# board1_7.net
KiCad netlist of a schematic drawn in EAGLE
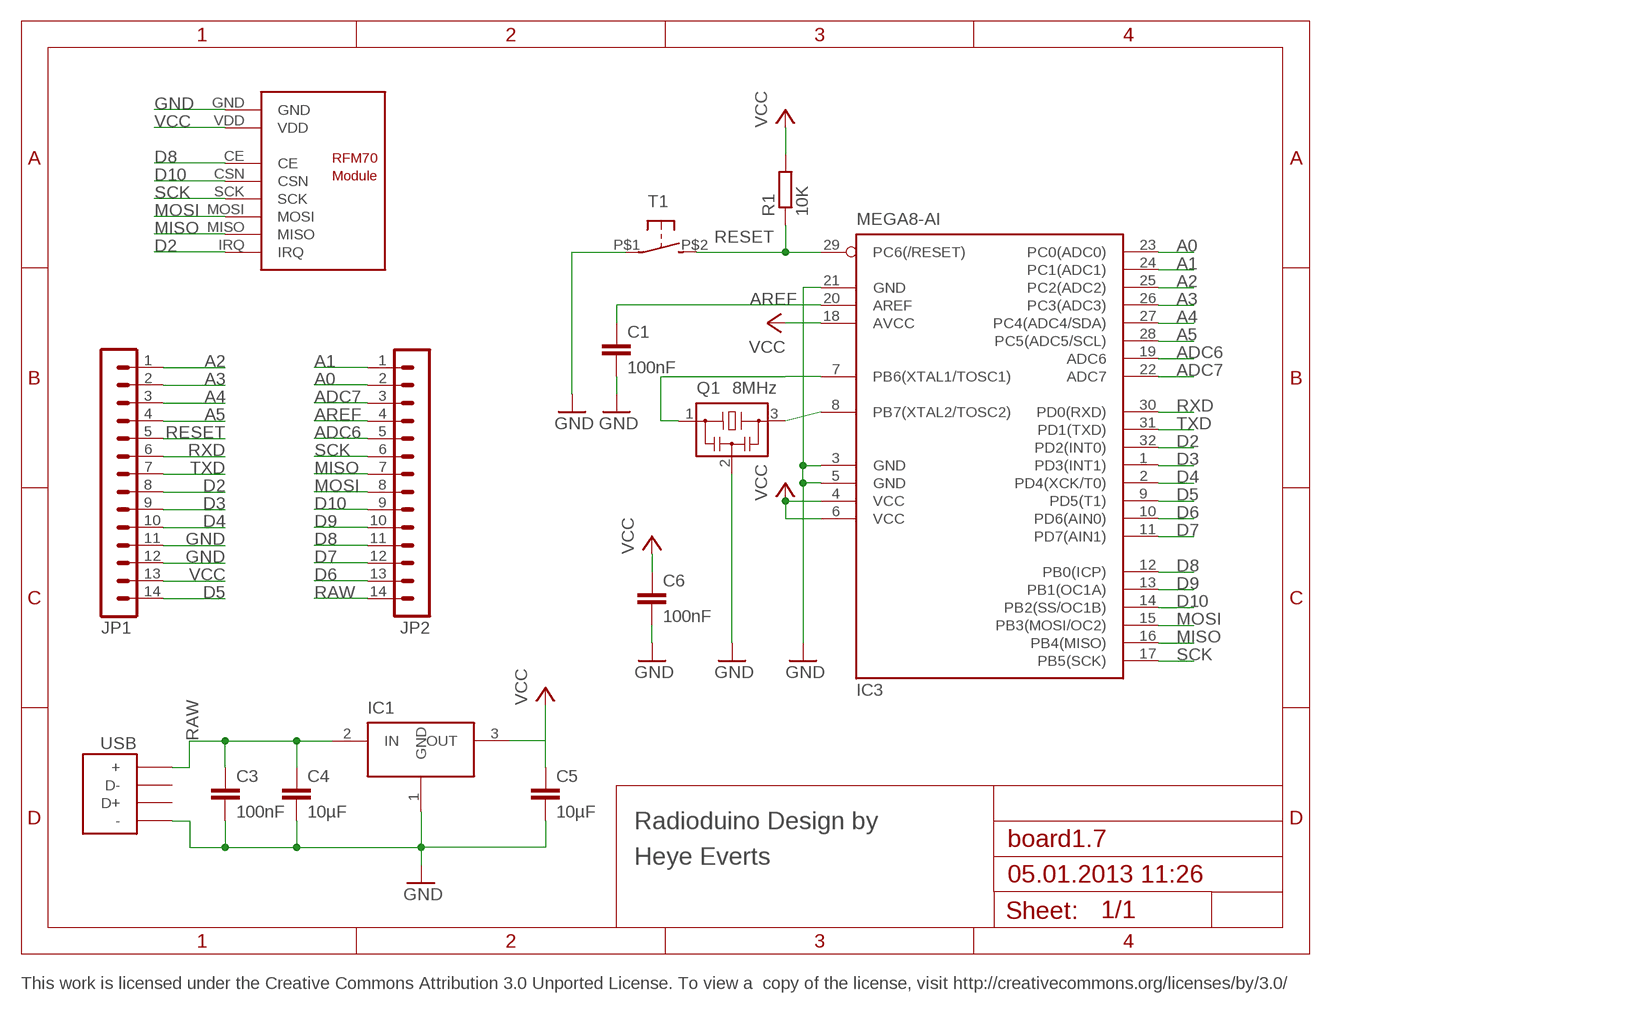
[diagram p0: schematic, sheet 1]

(export (version "E")
  (design (tool "Eeschema 10.0.6"))
  (components
    (comp (ref "C1")
      (value "100nF")
      (footprint "eagle-import:C0603K")
      (libsource (lib "eagle-import") (part "C-EUC0603K"))
    )
    (comp (ref "C3")
      (value "100nF")
      (footprint "eagle-import:C0603K")
      (libsource (lib "eagle-import") (part "C-EUC0603K"))
    )
    (comp (ref "C4")
      (value "10µF")
      (footprint "eagle-import:C0805K")
      (libsource (lib "eagle-import") (part "C-EUC0805K"))
    )
    (comp (ref "C5")
      (value "10µF")
      (footprint "eagle-import:C0805K")
      (libsource (lib "eagle-import") (part "C-EUC0805K"))
    )
    (comp (ref "C6")
      (value "100nF")
      (footprint "eagle-import:C0603K")
      (libsource (lib "eagle-import") (part "C-EUC0603K"))
    )
    (comp (ref "IC1")
      (value "TS1117CP33")
      (footprint "eagle-import:TO252")
      (libsource (lib "eagle-import") (part "TS1117CP33"))
    )
    (comp (ref "IC3")
      (value "MEGA8-AI")
      (footprint "eagle-import:TQFP32-08")
      (fields (field (name "MPN") "ATMEGA8-16AU"))
      (libsource (lib "eagle-import") (part "MEGA8-AI"))
    )
    (comp (ref "JP1")
      (value "MA14-1")
      (footprint "eagle-import:MA14-1")
      (fields (field (name "OC_FARNELL") "unknown") (field (name "OC_NEWARK") "unknown"))
      (libsource (lib "eagle-import") (part "MA14-1"))
    )
    (comp (ref "JP2")
      (value "MA14-1")
      (footprint "eagle-import:MA14-1")
      (libsource (lib "eagle-import") (part "MA14-1"))
    )
    (comp (ref "Q1")
      (value "8MHz")
      (footprint "eagle-import:CSTCE8M00G52")
      (libsource (lib "eagle-import") (part "CSTCE8M00G52"))
    )
    (comp (ref "R1")
      (value "10K")
      (footprint "eagle-import:R0603")
      (libsource (lib "eagle-import") (part "R-EU_R0603"))
    )
    (comp (ref "RFM70")
      (value "RFM70")
      (footprint "eagle-import:RFM70")
      (libsource (lib "eagle-import") (part "RFM70"))
    )
    (comp (ref "T1")
      (value "DTSM-3")
      (footprint "eagle-import:DTSM31N")
      (libsource (lib "eagle-import") (part "DTSM-3"))
    )
    (comp (ref "USB")
      (value "USB-MICRO-B-RS")
      (footprint "eagle-import:USB-MICRO-B-RS")
      (libsource (lib "eagle-import") (part "USB-MICRO-B-RS"))
    )
  )
  (nets
    (net (code "1") (name "/A0") (class "Default")
      (node (ref "IC3") (pin "23") (pinfunction "PC0(ADC0)_23") (pintype "bidirectional"))
      (node (ref "JP2") (pin "2") (pinfunction "2_2") (pintype "passive"))
    )
    (net (code "2") (name "/A1") (class "Default")
      (node (ref "IC3") (pin "24") (pinfunction "PC1(ADC1)_24") (pintype "bidirectional"))
      (node (ref "JP2") (pin "1") (pinfunction "1_1") (pintype "passive"))
    )
    (net (code "3") (name "/A2") (class "Default")
      (node (ref "IC3") (pin "25") (pinfunction "PC2(ADC2)_25") (pintype "bidirectional"))
      (node (ref "JP1") (pin "1") (pinfunction "1_1") (pintype "passive"))
    )
    (net (code "4") (name "/A3") (class "Default")
      (node (ref "IC3") (pin "26") (pinfunction "PC3(ADC3)_26") (pintype "bidirectional"))
      (node (ref "JP1") (pin "2") (pinfunction "2_2") (pintype "passive"))
    )
    (net (code "5") (name "/A4") (class "Default")
      (node (ref "IC3") (pin "27") (pinfunction "PC4(ADC4/SDA)_27") (pintype "bidirectional"))
      (node (ref "JP1") (pin "3") (pinfunction "3_3") (pintype "passive"))
    )
    (net (code "6") (name "/A5") (class "Default")
      (node (ref "IC3") (pin "28") (pinfunction "PC5(ADC5/SCL)_28") (pintype "bidirectional"))
      (node (ref "JP1") (pin "4") (pinfunction "4_4") (pintype "passive"))
    )
    (net (code "7") (name "/ADC6") (class "Default")
      (node (ref "IC3") (pin "19") (pinfunction "ADC6_19") (pintype "bidirectional"))
      (node (ref "JP2") (pin "5") (pinfunction "5_5") (pintype "passive"))
    )
    (net (code "8") (name "/ADC7") (class "Default")
      (node (ref "IC3") (pin "22") (pinfunction "ADC7_22") (pintype "bidirectional"))
      (node (ref "JP2") (pin "3") (pinfunction "3_3") (pintype "passive"))
    )
    (net (code "9") (name "/AREF") (class "Default")
      (node (ref "C1") (pin "1") (pinfunction "1_1") (pintype "passive"))
      (node (ref "IC3") (pin "20") (pinfunction "AREF_20") (pintype "passive"))
      (node (ref "JP2") (pin "4") (pinfunction "4_4") (pintype "passive"))
    )
    (net (code "10") (name "/D2") (class "Default")
      (node (ref "IC3") (pin "32") (pinfunction "PD2(INT0)_32") (pintype "bidirectional"))
      (node (ref "JP1") (pin "8") (pinfunction "8_8") (pintype "passive"))
      (node (ref "RFM70") (pin "IRQ") (pinfunction "IRQ_IRQ") (pintype "bidirectional"))
    )
    (net (code "11") (name "/D3") (class "Default")
      (node (ref "IC3") (pin "1") (pinfunction "PD3(INT1)_1") (pintype "bidirectional"))
      (node (ref "JP1") (pin "9") (pinfunction "9_9") (pintype "passive"))
    )
    (net (code "12") (name "/D4") (class "Default")
      (node (ref "IC3") (pin "2") (pinfunction "PD4(XCK/T0)_2") (pintype "bidirectional"))
      (node (ref "JP1") (pin "10") (pinfunction "10_10") (pintype "passive"))
    )
    (net (code "13") (name "/D5") (class "Default")
      (node (ref "IC3") (pin "9") (pinfunction "PD5(T1)_9") (pintype "bidirectional"))
      (node (ref "JP1") (pin "14") (pinfunction "14_14") (pintype "passive"))
    )
    (net (code "14") (name "/D6") (class "Default")
      (node (ref "IC3") (pin "10") (pinfunction "PD6(AIN0)_10") (pintype "bidirectional"))
      (node (ref "JP2") (pin "13") (pinfunction "13_13") (pintype "passive"))
    )
    (net (code "15") (name "/D7") (class "Default")
      (node (ref "IC3") (pin "11") (pinfunction "PD7(AIN1)_11") (pintype "bidirectional"))
      (node (ref "JP2") (pin "12") (pinfunction "12_12") (pintype "passive"))
    )
    (net (code "16") (name "/D8") (class "Default")
      (node (ref "IC3") (pin "12") (pinfunction "PB0(ICP)_12") (pintype "bidirectional"))
      (node (ref "JP2") (pin "11") (pinfunction "11_11") (pintype "passive"))
      (node (ref "RFM70") (pin "CE") (pinfunction "CE_CE") (pintype "bidirectional"))
    )
    (net (code "17") (name "/D9") (class "Default")
      (node (ref "IC3") (pin "13") (pinfunction "PB1(OC1A)_13") (pintype "bidirectional"))
      (node (ref "JP2") (pin "10") (pinfunction "10_10") (pintype "passive"))
    )
    (net (code "18") (name "/D10") (class "Default")
      (node (ref "IC3") (pin "14") (pinfunction "PB2(SS/OC1B)_14") (pintype "bidirectional"))
      (node (ref "JP2") (pin "9") (pinfunction "9_9") (pintype "passive"))
      (node (ref "RFM70") (pin "CSN") (pinfunction "CSN_CSN") (pintype "bidirectional"))
    )
    (net (code "19") (name "/MISO") (class "Default")
      (node (ref "IC3") (pin "16") (pinfunction "PB4(MISO)_16") (pintype "bidirectional"))
      (node (ref "JP2") (pin "7") (pinfunction "7_7") (pintype "passive"))
      (node (ref "RFM70") (pin "MISO") (pinfunction "MISO_MISO") (pintype "bidirectional"))
    )
    (net (code "20") (name "/MOSI") (class "Default")
      (node (ref "IC3") (pin "15") (pinfunction "PB3(MOSI/OC2)_15") (pintype "bidirectional"))
      (node (ref "JP2") (pin "8") (pinfunction "8_8") (pintype "passive"))
      (node (ref "RFM70") (pin "MOSI") (pinfunction "MOSI_MOSI") (pintype "bidirectional"))
    )
    (net (code "21") (name "/RAW") (class "Default")
      (node (ref "C3") (pin "1") (pinfunction "1_1") (pintype "passive"))
      (node (ref "C4") (pin "1") (pinfunction "1_1") (pintype "passive"))
      (node (ref "IC1") (pin "2") (pinfunction "IN_2") (pintype "bidirectional"))
      (node (ref "JP2") (pin "14") (pinfunction "14_14") (pintype "passive"))
      (node (ref "USB") (pin "P$1") (pinfunction "+_P$1") (pintype "bidirectional"))
    )
    (net (code "22") (name "/RESET") (class "Default")
      (node (ref "IC3") (pin "29") (pinfunction "PC6(/RESET)_29") (pintype "bidirectional"))
      (node (ref "JP1") (pin "5") (pinfunction "5_5") (pintype "passive"))
      (node (ref "R1") (pin "1") (pinfunction "1_1") (pintype "passive"))
      (node (ref "T1") (pin "P$2") (pinfunction "S_P$2") (pintype "passive"))
    )
    (net (code "23") (name "/RXD") (class "Default")
      (node (ref "IC3") (pin "30") (pinfunction "PD0(RXD)_30") (pintype "bidirectional"))
      (node (ref "JP1") (pin "6") (pinfunction "6_6") (pintype "passive"))
    )
    (net (code "24") (name "/SCK") (class "Default")
      (node (ref "IC3") (pin "17") (pinfunction "PB5(SCK)_17") (pintype "bidirectional"))
      (node (ref "JP2") (pin "6") (pinfunction "6_6") (pintype "passive"))
      (node (ref "RFM70") (pin "SCK") (pinfunction "SCK_SCK") (pintype "bidirectional"))
    )
    (net (code "25") (name "/TXD") (class "Default")
      (node (ref "IC3") (pin "31") (pinfunction "PD1(TXD)_31") (pintype "bidirectional"))
      (node (ref "JP1") (pin "7") (pinfunction "7_7") (pintype "passive"))
    )
    (net (code "26") (name "GND") (class "Default")
      (node (ref "C1") (pin "2") (pinfunction "2_2") (pintype "passive"))
      (node (ref "C3") (pin "2") (pinfunction "2_2") (pintype "passive"))
      (node (ref "C4") (pin "2") (pinfunction "2_2") (pintype "passive"))
      (node (ref "C5") (pin "2") (pinfunction "2_2") (pintype "passive"))
      (node (ref "C6") (pin "2") (pinfunction "2_2") (pintype "passive"))
      (node (ref "IC1") (pin "1") (pinfunction "GND_1") (pintype "bidirectional"))
      (node (ref "IC3") (pin "21") (pinfunction "GND_21") (pintype "power_in"))
      (node (ref "IC3") (pin "3") (pinfunction "GND_3") (pintype "power_in"))
      (node (ref "IC3") (pin "5") (pinfunction "GND_5") (pintype "power_in"))
      (node (ref "JP1") (pin "11") (pinfunction "11_11") (pintype "passive"))
      (node (ref "JP1") (pin "12") (pinfunction "12_12") (pintype "passive"))
      (node (ref "Q1") (pin "2") (pinfunction "2_2") (pintype "passive"))
      (node (ref "RFM70") (pin "GND") (pinfunction "GND_GND") (pintype "power_in"))
      (node (ref "T1") (pin "P$1") (pinfunction "P_P$1") (pintype "passive"))
      (node (ref "USB") (pin "P$5") (pinfunction "-_P$5") (pintype "bidirectional"))
    )
    (net (code "27") (name "Net-(IC3-PB6(XTAL1{slash}TOSC1))") (class "Default")
      (node (ref "IC3") (pin "7") (pinfunction "PB6(XTAL1/TOSC1)_7") (pintype "bidirectional"))
      (node (ref "Q1") (pin "1") (pinfunction "1_1") (pintype "passive"))
    )
    (net (code "28") (name "Net-(IC3-PB7(XTAL2{slash}TOSC2))") (class "Default")
      (node (ref "IC3") (pin "8") (pinfunction "PB7(XTAL2/TOSC2)_8") (pintype "bidirectional"))
      (node (ref "Q1") (pin "3") (pinfunction "3_3") (pintype "passive"))
    )
    (net (code "29") (name "VCC") (class "Default")
      (node (ref "C5") (pin "1") (pinfunction "1_1") (pintype "passive"))
      (node (ref "C6") (pin "1") (pinfunction "1_1") (pintype "passive"))
      (node (ref "IC1") (pin "3") (pinfunction "OUT_3") (pintype "bidirectional"))
      (node (ref "IC3") (pin "18") (pinfunction "AVCC_18") (pintype "power_in"))
      (node (ref "IC3") (pin "4") (pinfunction "VCC_4") (pintype "power_in"))
      (node (ref "IC3") (pin "6") (pinfunction "VCC_6") (pintype "power_in"))
      (node (ref "JP1") (pin "13") (pinfunction "13_13") (pintype "passive"))
      (node (ref "R1") (pin "2") (pinfunction "2_2") (pintype "passive"))
      (node (ref "RFM70") (pin "VDD") (pinfunction "VDD_VDD") (pintype "power_in"))
    )
    (net (code "30") (name "unconnected-(USB-D+-PadP$3)") (class "Default")
      (node (ref "USB") (pin "P$3") (pinfunction "D+_P$3") (pintype "bidirectional"))
    )
    (net (code "31") (name "unconnected-(USB-D--PadP$2)") (class "Default")
      (node (ref "USB") (pin "P$2") (pinfunction "D-_P$2") (pintype "bidirectional"))
    )
  )
)
